# Power_Supply.net
KiCad netlist of a schematic drawn in Altium Designer
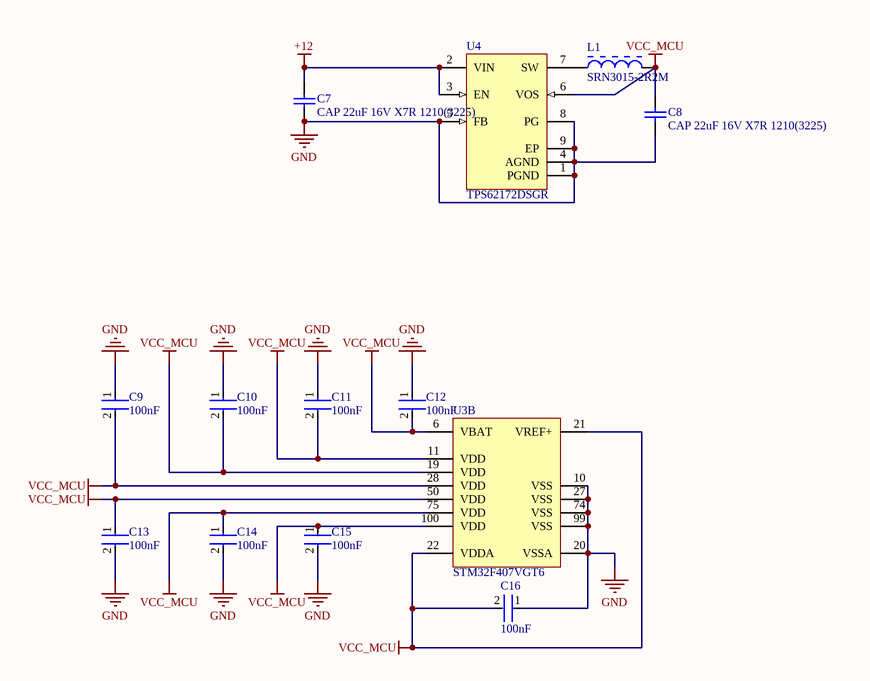
[diagram p0: Power_Supply.SchDoc]

(export (version "E")
  (design (tool "Eeschema 10.0.6"))
  (components
    (comp (ref "C7")
      (value "CAP 22uF 16V X7R 1210(3225)")
      (footprint "CAPC1210(3225)280_L")
      (description "CAP 22uF 16V ±10% 1210 (3225 Metric) Thickness 2.8mm SMD")
      (fields (field (name "TOLERANCE") "Â±10%"))
      (libsource (lib "Altium Content Vault") (part "CAP"))
    )
    (comp (ref "C8")
      (value "CAP 22uF 16V X7R 1210(3225)")
      (footprint "CAPC1210(3225)280_L")
      (description "CAP 22uF 16V ±10% 1210 (3225 Metric) Thickness 2.8mm SMD")
      (fields (field (name "TOLERANCE") "Â±10%"))
      (libsource (lib "Altium Content Vault") (part "CAP"))
    )
    (comp (ref "C9")
      (value "100nF")
      (footprint "Kemet_C0603_IPC_A")
      (description "CAP CER 0.1UF 100NF 50V X7R 0603 C0603C104K5RACTU")
      (libsource (lib "UNK_Kemet_C0603C104K5RACTU_eec") (part "C0603C104K5RACTU"))
    )
    (comp (ref "C10")
      (value "100nF")
      (footprint "Kemet_C0603_IPC_A")
      (description "CAP CER 0.1UF 100NF 50V X7R 0603 C0603C104K5RACTU")
      (libsource (lib "UNK_Kemet_C0603C104K5RACTU_eec") (part "C0603C104K5RACTU"))
    )
    (comp (ref "C11")
      (value "100nF")
      (footprint "Kemet_C0603_IPC_A")
      (description "CAP CER 0.1UF 100NF 50V X7R 0603 C0603C104K5RACTU")
      (libsource (lib "UNK_Kemet_C0603C104K5RACTU_eec") (part "C0603C104K5RACTU"))
    )
    (comp (ref "C12")
      (value "100nF")
      (footprint "Kemet_C0603_IPC_A")
      (description "CAP CER 0.1UF 100NF 50V X7R 0603 C0603C104K5RACTU")
      (libsource (lib "UNK_Kemet_C0603C104K5RACTU_eec") (part "C0603C104K5RACTU"))
    )
    (comp (ref "C13")
      (value "100nF")
      (footprint "Kemet_C0603_IPC_A")
      (description "CAP CER 0.1UF 100NF 50V X7R 0603 C0603C104K5RACTU")
      (libsource (lib "UNK_Kemet_C0603C104K5RACTU_eec") (part "C0603C104K5RACTU"))
    )
    (comp (ref "C14")
      (value "100nF")
      (footprint "Kemet_C0603_IPC_A")
      (description "CAP CER 0.1UF 100NF 50V X7R 0603 C0603C104K5RACTU")
      (libsource (lib "UNK_Kemet_C0603C104K5RACTU_eec") (part "C0603C104K5RACTU"))
    )
    (comp (ref "C15")
      (value "100nF")
      (footprint "Kemet_C0603_IPC_A")
      (description "CAP CER 0.1UF 100NF 50V X7R 0603 C0603C104K5RACTU")
      (libsource (lib "UNK_Kemet_C0603C104K5RACTU_eec") (part "C0603C104K5RACTU"))
    )
    (comp (ref "C16")
      (value "100nF")
      (footprint "Kemet_C0603_IPC_A")
      (description "CAP CER 0.1UF 100NF 50V X7R 0603 C0603C104K5RACTU")
      (libsource (lib "UNK_Kemet_C0603C104K5RACTU_eec") (part "C0603C104K5RACTU"))
    )
    (comp (ref "L1")
      (value "SRN3015-2R2M")
      (footprint "BOUR-SRN3015-2_V")
      (fields (field (name "MANUFACTURER") "Bourns"))
      (libsource (lib "Altium Content Vault") (part "BOUR-IND-2A"))
    )
    (comp (ref "U3")
      (value "STM32F407VGT6")
      (footprint "STM-LQFP100_M")
      (fields (field (name "MANUFACTURER") "STMicroelectronics"))
      (libsource (lib "Altium Content Vault") (part "MC-ARM-STM32F40X_41X-SQ100"))
    )
    (comp (ref "U4")
      (value "TPS62172DSGR")
      (footprint "DSG8-1600X900TP")
      (fields (field (name "MANUFACTURER") "Texas Instruments"))
      (libsource (lib "Texas_Instruments_TPS62172DSGR") (part "TPS62172DSGR"))
    )
  )
  (nets
    (net (code "1") (name "+12") (class "Default")
      (node (ref "C7") (pin "2") (pinfunction "2_2") (pintype "passive"))
      (node (ref "U4") (pin "2") (pinfunction "VIN_2") (pintype "power_in"))
      (node (ref "U4") (pin "3") (pinfunction "EN_3") (pintype "input"))
    )
    (net (code "2") (name "GND") (class "Default")
      (node (ref "C10") (pin "1") (pinfunction "1_1") (pintype "passive"))
      (node (ref "C11") (pin "1") (pinfunction "1_1") (pintype "passive"))
      (node (ref "C12") (pin "1") (pinfunction "1_1") (pintype "passive"))
      (node (ref "C13") (pin "2") (pinfunction "2_2") (pintype "passive"))
      (node (ref "C14") (pin "2") (pinfunction "2_2") (pintype "passive"))
      (node (ref "C15") (pin "2") (pinfunction "2_2") (pintype "passive"))
      (node (ref "C16") (pin "1") (pinfunction "1_1") (pintype "passive"))
      (node (ref "C7") (pin "1") (pinfunction "1_1") (pintype "passive"))
      (node (ref "C8") (pin "1") (pinfunction "1_1") (pintype "passive"))
      (node (ref "C9") (pin "1") (pinfunction "1_1") (pintype "passive"))
      (node (ref "U3") (pin "10") (pinfunction "VSS_10") (pintype "power_in"))
      (node (ref "U3") (pin "20") (pinfunction "VSSA_20") (pintype "power_in"))
      (node (ref "U3") (pin "27") (pinfunction "VSS_27") (pintype "power_in"))
      (node (ref "U3") (pin "74") (pinfunction "VSS_74") (pintype "power_in"))
      (node (ref "U3") (pin "99") (pinfunction "VSS_99") (pintype "power_in"))
      (node (ref "U4") (pin "1") (pinfunction "PGND_1") (pintype "power_in"))
      (node (ref "U4") (pin "4") (pinfunction "AGND_4") (pintype "power_in"))
      (node (ref "U4") (pin "5") (pinfunction "FB_5") (pintype "input"))
      (node (ref "U4") (pin "8") (pinfunction "PG_8") (pintype "passive"))
      (node (ref "U4") (pin "9") (pinfunction "EP_9") (pintype "power_in"))
    )
    (net (code "3") (name "Net-(U4-SW)") (class "Default")
      (node (ref "L1") (pin "1") (pinfunction "1_1") (pintype "passive"))
      (node (ref "U4") (pin "7") (pinfunction "SW_7") (pintype "power_in"))
    )
    (net (code "4") (name "VCC_MCU") (class "Default")
      (node (ref "C10") (pin "2") (pinfunction "2_2") (pintype "passive"))
      (node (ref "C11") (pin "2") (pinfunction "2_2") (pintype "passive"))
      (node (ref "C12") (pin "2") (pinfunction "2_2") (pintype "passive"))
      (node (ref "C13") (pin "1") (pinfunction "1_1") (pintype "passive"))
      (node (ref "C14") (pin "1") (pinfunction "1_1") (pintype "passive"))
      (node (ref "C15") (pin "1") (pinfunction "1_1") (pintype "passive"))
      (node (ref "C16") (pin "2") (pinfunction "2_2") (pintype "passive"))
      (node (ref "C8") (pin "2") (pinfunction "2_2") (pintype "passive"))
      (node (ref "C9") (pin "2") (pinfunction "2_2") (pintype "passive"))
      (node (ref "L1") (pin "2") (pinfunction "2_2") (pintype "passive"))
      (node (ref "U3") (pin "100") (pinfunction "VDD_100") (pintype "power_in"))
      (node (ref "U3") (pin "11") (pinfunction "VDD_11") (pintype "power_in"))
      (node (ref "U3") (pin "19") (pinfunction "VDD_19") (pintype "power_in"))
      (node (ref "U3") (pin "21") (pinfunction "VREF+_21") (pintype "power_in"))
      (node (ref "U3") (pin "22") (pinfunction "VDDA_22") (pintype "power_in"))
      (node (ref "U3") (pin "28") (pinfunction "VDD_28") (pintype "power_in"))
      (node (ref "U3") (pin "50") (pinfunction "VDD_50") (pintype "power_in"))
      (node (ref "U3") (pin "6") (pinfunction "VBAT_6") (pintype "power_in"))
      (node (ref "U3") (pin "75") (pinfunction "VDD_75") (pintype "power_in"))
      (node (ref "U4") (pin "6") (pinfunction "VOS_6") (pintype "input"))
    )
  )
)
